# L298.net
KiCad netlist of a schematic drawn in Altium Designer
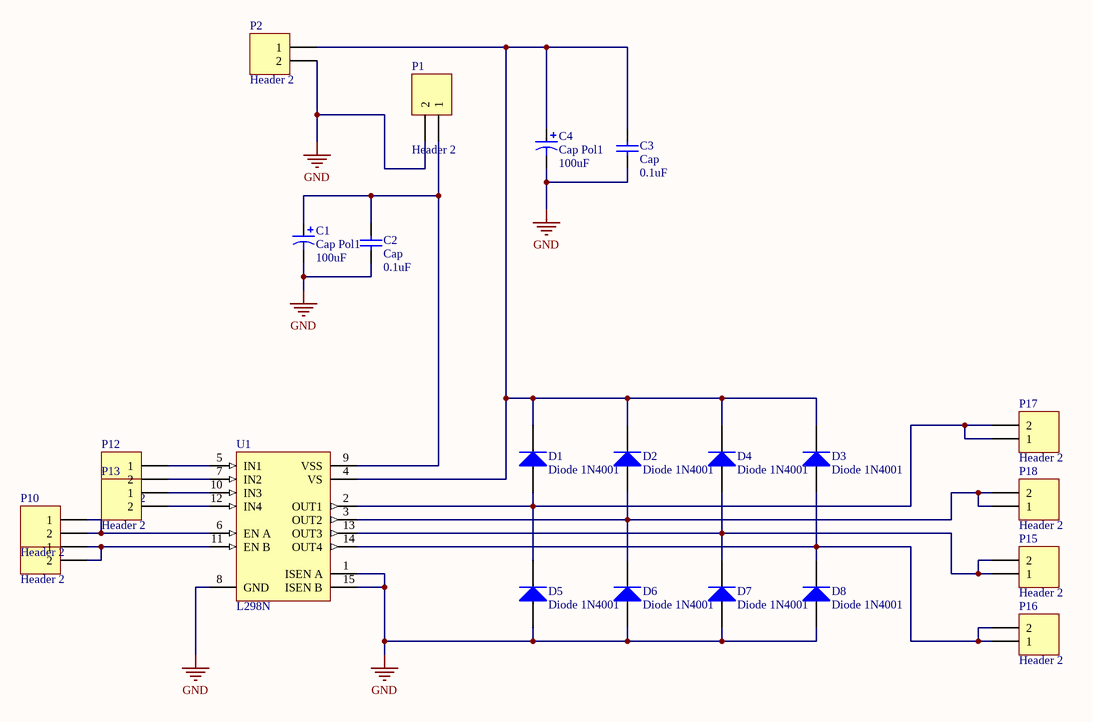
[diagram p0: L298.SchDoc]

(export (version "E")
  (design (tool "Eeschema 10.0.6"))
  (components
    (comp (ref "C1")
      (value "Cap Pol1")
      (footprint "RB7.6-15")
      (description "Polarized Capacitor (Radial)")
      (fields (field (name "ALTIUM_VALUE") "100uF") (field (name "PUBLISHER") "Altium Limited"))
      (libsource (lib "Miscellaneous Devices") (part "Cap Pol1"))
    )
    (comp (ref "C2")
      (value "Cap")
      (footprint "RAD-0.3")
      (description "Capacitor")
      (fields (field (name "ALTIUM_VALUE") "0.1uF") (field (name "PUBLISHER") "Altium Limited"))
      (libsource (lib "Miscellaneous Devices") (part "Cap"))
    )
    (comp (ref "C3")
      (value "Cap")
      (footprint "RAD-0.3")
      (description "Capacitor")
      (fields (field (name "ALTIUM_VALUE") "0.1uF") (field (name "PUBLISHER") "Altium Limited"))
      (libsource (lib "Miscellaneous Devices") (part "Cap"))
    )
    (comp (ref "C4")
      (value "Cap Pol1")
      (footprint "RB7.6-15")
      (description "Polarized Capacitor (Radial)")
      (fields (field (name "ALTIUM_VALUE") "100uF") (field (name "PUBLISHER") "Altium Limited"))
      (libsource (lib "Miscellaneous Devices") (part "Cap Pol1"))
    )
    (comp (ref "D1")
      (value "Diode 1N4001")
      (footprint "DO-41")
      (description "1 Amp General Purpose Rectifier")
      (fields (field (name "PUBLISHER") "Altium Limited"))
      (libsource (lib "Miscellaneous Devices") (part "Diode 1N4001"))
    )
    (comp (ref "D2")
      (value "Diode 1N4001")
      (footprint "DO-41")
      (description "1 Amp General Purpose Rectifier")
      (fields (field (name "PUBLISHER") "Altium Limited"))
      (libsource (lib "Miscellaneous Devices") (part "Diode 1N4001"))
    )
    (comp (ref "D3")
      (value "Diode 1N4001")
      (footprint "DO-41")
      (description "1 Amp General Purpose Rectifier")
      (fields (field (name "PUBLISHER") "Altium Limited"))
      (libsource (lib "Miscellaneous Devices") (part "Diode 1N4001"))
    )
    (comp (ref "D4")
      (value "Diode 1N4001")
      (footprint "DO-41")
      (description "1 Amp General Purpose Rectifier")
      (fields (field (name "PUBLISHER") "Altium Limited"))
      (libsource (lib "Miscellaneous Devices") (part "Diode 1N4001"))
    )
    (comp (ref "D5")
      (value "Diode 1N4001")
      (footprint "DO-41")
      (description "1 Amp General Purpose Rectifier")
      (fields (field (name "PUBLISHER") "Altium Limited"))
      (libsource (lib "Miscellaneous Devices") (part "Diode 1N4001"))
    )
    (comp (ref "D6")
      (value "Diode 1N4001")
      (footprint "DO-41")
      (description "1 Amp General Purpose Rectifier")
      (fields (field (name "PUBLISHER") "Altium Limited"))
      (libsource (lib "Miscellaneous Devices") (part "Diode 1N4001"))
    )
    (comp (ref "D7")
      (value "Diode 1N4001")
      (footprint "DO-41")
      (description "1 Amp General Purpose Rectifier")
      (fields (field (name "PUBLISHER") "Altium Limited"))
      (libsource (lib "Miscellaneous Devices") (part "Diode 1N4001"))
    )
    (comp (ref "D8")
      (value "Diode 1N4001")
      (footprint "DO-41")
      (description "1 Amp General Purpose Rectifier")
      (fields (field (name "PUBLISHER") "Altium Limited"))
      (libsource (lib "Miscellaneous Devices") (part "Diode 1N4001"))
    )
    (comp (ref "P1")
      (value "Header 2")
      (footprint "HDR1X2")
      (description "Header, 2-Pin")
      (fields (field (name "PUBLISHER") "Altium Limited"))
      (libsource (lib "") (part "Header 2_2"))
    )
    (comp (ref "P2")
      (value "Header 2")
      (footprint "HDR1X2")
      (description "Header, 2-Pin")
      (fields (field (name "PUBLISHER") "Altium Limited"))
      (libsource (lib "Miscellaneous Connectors") (part "Header 2"))
    )
    (comp (ref "P10")
      (value "Header 2")
      (footprint "HDR1X2")
      (description "Header, 2-Pin")
      (fields (field (name "PUBLISHER") "Altium Limited"))
      (libsource (lib "Miscellaneous Connectors") (part "Header 2"))
    )
    (comp (ref "P11")
      (value "Header 2")
      (footprint "HDR1X2")
      (description "Header, 2-Pin")
      (fields (field (name "PUBLISHER") "Altium Limited"))
      (libsource (lib "Miscellaneous Connectors") (part "Header 2"))
    )
    (comp (ref "P12")
      (value "Header 2")
      (footprint "HDR1X2")
      (description "Header, 2-Pin")
      (fields (field (name "PUBLISHER") "Altium Limited"))
      (libsource (lib "Miscellaneous Connectors") (part "Header 2"))
    )
    (comp (ref "P13")
      (value "Header 2")
      (footprint "HDR1X2")
      (description "Header, 2-Pin")
      (fields (field (name "PUBLISHER") "Altium Limited"))
      (libsource (lib "Miscellaneous Connectors") (part "Header 2"))
    )
    (comp (ref "P15")
      (value "Header 2")
      (footprint "HDR1X2")
      (description "Header, 2-Pin")
      (fields (field (name "PUBLISHER") "Altium Limited"))
      (libsource (lib "") (part "Header 2_1"))
    )
    (comp (ref "P16")
      (value "Header 2")
      (footprint "HDR1X2")
      (description "Header, 2-Pin")
      (fields (field (name "PUBLISHER") "Altium Limited"))
      (libsource (lib "") (part "Header 2_1"))
    )
    (comp (ref "P17")
      (value "Header 2")
      (footprint "HDR1X2")
      (description "Header, 2-Pin")
      (fields (field (name "PUBLISHER") "Altium Limited"))
      (libsource (lib "") (part "Header 2_1"))
    )
    (comp (ref "P18")
      (value "Header 2")
      (footprint "HDR1X2")
      (description "Header, 2-Pin")
      (fields (field (name "PUBLISHER") "Altium Limited"))
      (libsource (lib "") (part "Header 2_1"))
    )
    (comp (ref "U1")
      (value "L298N")
      (footprint "Multiwatt15V")
      (description "Dual Full Bridge Driver")
      (fields (field (name "PUBLISHER") "Altium Limited"))
      (libsource (lib "ST Interface DC Motor Controller") (part "L298N"))
    )
  )
  (nets
    (net (code "1") (name "GND") (class "Default")
      (node (ref "C1") (pin "2") (pinfunction "2_2") (pintype "passive"))
      (node (ref "C2") (pin "1") (pinfunction "1_1") (pintype "passive"))
      (node (ref "C3") (pin "1") (pinfunction "1_1") (pintype "passive"))
      (node (ref "C4") (pin "2") (pinfunction "2_2") (pintype "passive"))
      (node (ref "D5") (pin "1") (pinfunction "A_1") (pintype "passive"))
      (node (ref "D6") (pin "1") (pinfunction "A_1") (pintype "passive"))
      (node (ref "D7") (pin "1") (pinfunction "A_1") (pintype "passive"))
      (node (ref "D8") (pin "1") (pinfunction "A_1") (pintype "passive"))
      (node (ref "P1") (pin "2") (pinfunction "2_2") (pintype "passive"))
      (node (ref "P2") (pin "2") (pinfunction "2_2") (pintype "passive"))
      (node (ref "U1") (pin "1") (pinfunction "ISEN_A_1") (pintype "passive"))
      (node (ref "U1") (pin "15") (pinfunction "ISEN_B_15") (pintype "passive"))
      (node (ref "U1") (pin "8") (pinfunction "GND_8") (pintype "power_in"))
    )
    (net (code "2") (name "Net-(D1-A)") (class "Default")
      (node (ref "D1") (pin "1") (pinfunction "A_1") (pintype "passive"))
      (node (ref "D5") (pin "2") (pinfunction "K_2") (pintype "passive"))
      (node (ref "P17") (pin "1") (pinfunction "1_1") (pintype "passive"))
      (node (ref "P17") (pin "2") (pinfunction "2_2") (pintype "passive"))
      (node (ref "U1") (pin "2") (pinfunction "OUT1_2") (pintype "output"))
    )
    (net (code "3") (name "Net-(D1-K)") (class "Default")
      (node (ref "C3") (pin "2") (pinfunction "2_2") (pintype "passive"))
      (node (ref "C4") (pin "1") (pinfunction "1_1") (pintype "passive"))
      (node (ref "D1") (pin "2") (pinfunction "K_2") (pintype "passive"))
      (node (ref "D2") (pin "2") (pinfunction "K_2") (pintype "passive"))
      (node (ref "D3") (pin "2") (pinfunction "K_2") (pintype "passive"))
      (node (ref "D4") (pin "2") (pinfunction "K_2") (pintype "passive"))
      (node (ref "P2") (pin "1") (pinfunction "1_1") (pintype "passive"))
      (node (ref "U1") (pin "4") (pinfunction "VS_4") (pintype "power_in"))
    )
    (net (code "4") (name "Net-(D2-A)") (class "Default")
      (node (ref "D2") (pin "1") (pinfunction "A_1") (pintype "passive"))
      (node (ref "D6") (pin "2") (pinfunction "K_2") (pintype "passive"))
      (node (ref "P18") (pin "1") (pinfunction "1_1") (pintype "passive"))
      (node (ref "P18") (pin "2") (pinfunction "2_2") (pintype "passive"))
      (node (ref "U1") (pin "3") (pinfunction "OUT2_3") (pintype "output"))
    )
    (net (code "5") (name "Net-(D3-A)") (class "Default")
      (node (ref "D3") (pin "1") (pinfunction "A_1") (pintype "passive"))
      (node (ref "D8") (pin "2") (pinfunction "K_2") (pintype "passive"))
      (node (ref "P16") (pin "1") (pinfunction "1_1") (pintype "passive"))
      (node (ref "P16") (pin "2") (pinfunction "2_2") (pintype "passive"))
      (node (ref "U1") (pin "14") (pinfunction "OUT4_14") (pintype "output"))
    )
    (net (code "6") (name "Net-(D4-A)") (class "Default")
      (node (ref "D4") (pin "1") (pinfunction "A_1") (pintype "passive"))
      (node (ref "D7") (pin "2") (pinfunction "K_2") (pintype "passive"))
      (node (ref "P15") (pin "1") (pinfunction "1_1") (pintype "passive"))
      (node (ref "P15") (pin "2") (pinfunction "2_2") (pintype "passive"))
      (node (ref "U1") (pin "13") (pinfunction "OUT3_13") (pintype "output"))
    )
    (net (code "7") (name "Net-(U1-EN_A)") (class "Default")
      (node (ref "P10") (pin "1") (pinfunction "1_1") (pintype "passive"))
      (node (ref "P10") (pin "2") (pinfunction "2_2") (pintype "passive"))
      (node (ref "U1") (pin "6") (pinfunction "EN_A_6") (pintype "input"))
    )
    (net (code "8") (name "Net-(U1-EN_B)") (class "Default")
      (node (ref "P11") (pin "1") (pinfunction "1_1") (pintype "passive"))
      (node (ref "P11") (pin "2") (pinfunction "2_2") (pintype "passive"))
      (node (ref "U1") (pin "11") (pinfunction "EN_B_11") (pintype "input"))
    )
    (net (code "9") (name "Net-(U1-IN1)") (class "Default")
      (node (ref "P12") (pin "1") (pinfunction "1_1") (pintype "passive"))
      (node (ref "U1") (pin "5") (pinfunction "IN1_5") (pintype "input"))
    )
    (net (code "10") (name "Net-(U1-IN2)") (class "Default")
      (node (ref "P12") (pin "2") (pinfunction "2_2") (pintype "passive"))
      (node (ref "U1") (pin "7") (pinfunction "IN2_7") (pintype "input"))
    )
    (net (code "11") (name "Net-(U1-IN3)") (class "Default")
      (node (ref "P13") (pin "1") (pinfunction "1_1") (pintype "passive"))
      (node (ref "U1") (pin "10") (pinfunction "IN3_10") (pintype "input"))
    )
    (net (code "12") (name "Net-(U1-IN4)") (class "Default")
      (node (ref "P13") (pin "2") (pinfunction "2_2") (pintype "passive"))
      (node (ref "U1") (pin "12") (pinfunction "IN4_12") (pintype "input"))
    )
    (net (code "13") (name "Net-(U1-VSS)") (class "Default")
      (node (ref "C1") (pin "1") (pinfunction "1_1") (pintype "passive"))
      (node (ref "C2") (pin "2") (pinfunction "2_2") (pintype "passive"))
      (node (ref "P1") (pin "1") (pinfunction "1_1") (pintype "passive"))
      (node (ref "U1") (pin "9") (pinfunction "VSS_9") (pintype "power_in"))
    )
  )
)
